# USB.net
KiCad netlist of a schematic drawn in Altium Designer
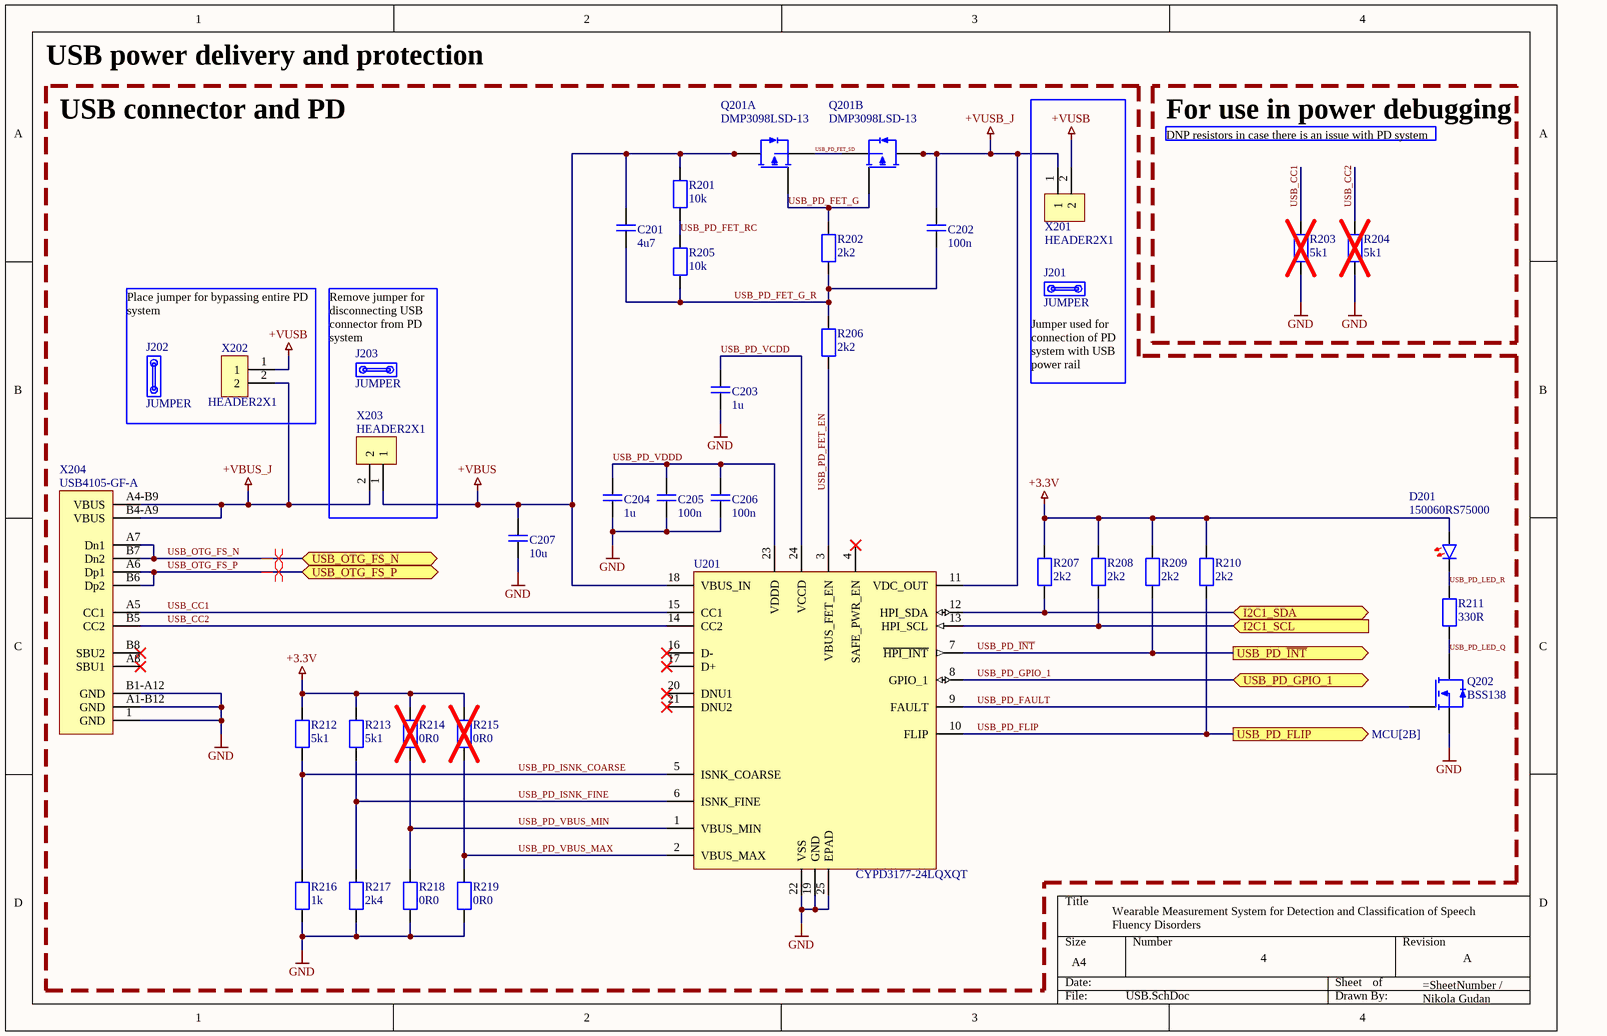
[diagram p0: USB.SchDoc]

(export (version "E")
  (design (tool "Eeschema 10.0.6"))
  (components
    (comp (ref "C201")
      (value "4u7")
      (footprint "CAPC0603")
      (description "Ceramic capacitor, VAL?,  VOL?, DIEL?")
      (fields (field (name "MFR") "?") (field (name "CHECKED") "Yes"))
      (libsource (lib "NG_Passive") (part "CAPC0603"))
    )
    (comp (ref "C202")
      (value "100n")
      (footprint "CAPC0603")
      (description "Ceramic capacitor, VAL?,  VOL?, DIEL?")
      (fields (field (name "MFR") "?") (field (name "CHECKED") "Yes"))
      (libsource (lib "NG_Passive") (part "CAPC0603"))
    )
    (comp (ref "C203")
      (value "1u")
      (footprint "CAPC0603")
      (description "Ceramic capacitor, VAL?,  VOL?, DIEL?")
      (fields (field (name "MFR") "?") (field (name "CHECKED") "Yes"))
      (libsource (lib "NG_Passive") (part "CAPC0603"))
    )
    (comp (ref "C204")
      (value "1u")
      (footprint "CAPC0603")
      (description "Ceramic capacitor, VAL?,  VOL?, DIEL?")
      (fields (field (name "MFR") "?") (field (name "CHECKED") "Yes"))
      (libsource (lib "NG_Passive") (part "CAPC0603"))
    )
    (comp (ref "C205")
      (value "100n")
      (footprint "CAPC0603")
      (description "Ceramic capacitor, VAL?,  VOL?, DIEL?")
      (fields (field (name "MFR") "?") (field (name "CHECKED") "Yes"))
      (libsource (lib "NG_Passive") (part "CAPC0603"))
    )
    (comp (ref "C206")
      (value "100n")
      (footprint "CAPC0603")
      (description "Ceramic capacitor, VAL?,  VOL?, DIEL?")
      (fields (field (name "MFR") "?") (field (name "CHECKED") "Yes"))
      (libsource (lib "NG_Passive") (part "CAPC0603"))
    )
    (comp (ref "C207")
      (value "10u")
      (footprint "CAPC0603")
      (description "Ceramic capacitor, VAL?,  VOL?, DIEL?")
      (fields (field (name "MFR") "?") (field (name "CHECKED") "Yes"))
      (libsource (lib "NG_Passive") (part "CAPC0603"))
    )
    (comp (ref "D201")
      (value "150060RS75000")
      (footprint "LED0603")
      (description "LED Red, 2.3V, 20mA")
      (fields
        (field (name "MFR") "Würth Elektronik")
        (field (name "LCSC PART NUMBER") "C497931")
        (field (name "CHECKED") "Yes")
      )
      (libsource (lib "NG_Active") (part "HL-PST-1608S9AC-04"))
    )
    (comp (ref "J201")
      (value "JUMPER")
      (description "Open Top 3A 2.54mm P=2.54mm Shunts & Jumpers ROHS")
      (fields
        (field (name "MFR") "Kycon, Inc.")
        (field (name "LCSC PART NUMBER") "C5305")
        (field (name "CHECKED") "Yes")
      )
      (libsource (lib "NG_Mechanical") (part "JUMPER"))
    )
    (comp (ref "J202")
      (value "JUMPER")
      (description "Open Top 3A 2.54mm P=2.54mm Shunts & Jumpers ROHS")
      (fields
        (field (name "MFR") "Kycon, Inc.")
        (field (name "LCSC PART NUMBER") "C5305")
        (field (name "CHECKED") "Yes")
      )
      (libsource (lib "NG_Mechanical") (part "JUMPER"))
    )
    (comp (ref "J203")
      (value "JUMPER")
      (description "Open Top 3A 2.54mm P=2.54mm Shunts & Jumpers ROHS")
      (fields
        (field (name "MFR") "Kycon, Inc.")
        (field (name "LCSC PART NUMBER") "C5305")
        (field (name "CHECKED") "Yes")
      )
      (libsource (lib "NG_Mechanical") (part "JUMPER"))
    )
    (comp (ref "Q201")
      (value "DMP3098LSD-13")
      (footprint "SOIC127P620X175-8")
      (description "MOSFET 2P-CH 30V 4.4A 8-SOIC")
      (fields
        (field (name "MFR") "Diodes Incorporated")
        (field (name "LCSC PART NUMBER") "C531177")
        (field (name "CHECKED") "Yes")
      )
      (libsource (lib "NG_Active") (part "DMP3098LSD-13"))
    )
    (comp (ref "Q202")
      (value "BSS138")
      (footprint "SOT190P240X290-3")
      (description "MOSFET N-CH 50V 220MA SOT23-3")
      (fields
        (field (name "MFR") "onsemi")
        (field (name "LCSC PART NUMBER") "C52895")
        (field (name "CHECKED") "Yes")
      )
      (libsource (lib "NG_Active") (part "BSS138"))
    )
    (comp (ref "R201")
      (value "10k")
      (footprint "RESC0603")
      (description "Thick film resistor, VAL?, POW?")
      (fields (field (name "MFR") "?") (field (name "CHECKED") "Yes"))
      (libsource (lib "NG_Passive") (part "RES0603"))
    )
    (comp (ref "R202")
      (value "2k2")
      (footprint "RESC0603")
      (description "Thick film resistor, VAL?, POW?")
      (fields (field (name "MFR") "?") (field (name "CHECKED") "Yes"))
      (libsource (lib "NG_Passive") (part "RES0603"))
    )
    (comp (ref "R203")
      (value "5k1")
      (footprint "RESC0603")
      (description "Thick film resistor, VAL?, POW?")
      (fields (field (name "MFR") "?") (field (name "CHECKED") "Yes"))
      (libsource (lib "NG_Passive") (part "RES0603"))
    )
    (comp (ref "R204")
      (value "5k1")
      (footprint "RESC0603")
      (description "Thick film resistor, VAL?, POW?")
      (fields (field (name "MFR") "?") (field (name "CHECKED") "Yes"))
      (libsource (lib "NG_Passive") (part "RES0603"))
    )
    (comp (ref "R205")
      (value "10k")
      (footprint "RESC0603")
      (description "Thick film resistor, VAL?, POW?")
      (fields (field (name "MFR") "?") (field (name "CHECKED") "Yes"))
      (libsource (lib "NG_Passive") (part "RES0603"))
    )
    (comp (ref "R206")
      (value "2k2")
      (footprint "RESC0603")
      (description "Thick film resistor, VAL?, POW?")
      (fields (field (name "MFR") "?") (field (name "CHECKED") "Yes"))
      (libsource (lib "NG_Passive") (part "RES0603"))
    )
    (comp (ref "R207")
      (value "2k2")
      (footprint "RESC0603")
      (description "Thick film resistor, VAL?, POW?")
      (fields (field (name "MFR") "?") (field (name "CHECKED") "Yes"))
      (libsource (lib "NG_Passive") (part "RES0603"))
    )
    (comp (ref "R208")
      (value "2k2")
      (footprint "RESC0603")
      (description "Thick film resistor, VAL?, POW?")
      (fields (field (name "MFR") "?") (field (name "CHECKED") "Yes"))
      (libsource (lib "NG_Passive") (part "RES0603"))
    )
    (comp (ref "R209")
      (value "2k2")
      (footprint "RESC0603")
      (description "Thick film resistor, VAL?, POW?")
      (fields (field (name "MFR") "?") (field (name "CHECKED") "Yes"))
      (libsource (lib "NG_Passive") (part "RES0603"))
    )
    (comp (ref "R210")
      (value "2k2")
      (footprint "RESC0603")
      (description "Thick film resistor, VAL?, POW?")
      (fields (field (name "MFR") "?") (field (name "CHECKED") "Yes"))
      (libsource (lib "NG_Passive") (part "RES0603"))
    )
    (comp (ref "R211")
      (value "330R")
      (footprint "RESC0603")
      (description "Thick film resistor, VAL?, POW?")
      (fields (field (name "MFR") "?") (field (name "CHECKED") "Yes"))
      (libsource (lib "NG_Passive") (part "RES0603"))
    )
    (comp (ref "R212")
      (value "5k1")
      (footprint "RESC0603")
      (description "Thick film resistor, VAL?, POW?")
      (fields (field (name "MFR") "?") (field (name "CHECKED") "Yes"))
      (libsource (lib "NG_Passive") (part "RES0603"))
    )
    (comp (ref "R213")
      (value "5k1")
      (footprint "RESC0603")
      (description "Thick film resistor, VAL?, POW?")
      (fields (field (name "MFR") "?") (field (name "CHECKED") "Yes"))
      (libsource (lib "NG_Passive") (part "RES0603"))
    )
    (comp (ref "R214")
      (value "0R0")
      (footprint "RESC0603")
      (description "Thick film resistor, VAL?, POW?")
      (fields (field (name "MFR") "?") (field (name "CHECKED") "Yes"))
      (libsource (lib "NG_Passive") (part "RES0603"))
    )
    (comp (ref "R215")
      (value "0R0")
      (footprint "RESC0603")
      (description "Thick film resistor, VAL?, POW?")
      (fields (field (name "MFR") "?") (field (name "CHECKED") "Yes"))
      (libsource (lib "NG_Passive") (part "RES0603"))
    )
    (comp (ref "R216")
      (value "1k")
      (footprint "RESC0603")
      (description "Thick film resistor, VAL?, POW?")
      (fields (field (name "MFR") "?") (field (name "CHECKED") "Yes"))
      (libsource (lib "NG_Passive") (part "RES0603"))
    )
    (comp (ref "R217")
      (value "2k4")
      (footprint "RESC0603")
      (description "Thick film resistor, VAL?, POW?")
      (fields (field (name "MFR") "?") (field (name "CHECKED") "Yes"))
      (libsource (lib "NG_Passive") (part "RES0603"))
    )
    (comp (ref "R218")
      (value "0R0")
      (footprint "RESC0603")
      (description "Thick film resistor, VAL?, POW?")
      (fields (field (name "MFR") "?") (field (name "CHECKED") "Yes"))
      (libsource (lib "NG_Passive") (part "RES0603"))
    )
    (comp (ref "R219")
      (value "0R0")
      (footprint "RESC0603")
      (description "Thick film resistor, VAL?, POW?")
      (fields (field (name "MFR") "?") (field (name "CHECKED") "Yes"))
      (libsource (lib "NG_Passive") (part "RES0603"))
    )
    (comp (ref "U201")
      (value "CYPD3177-24LQXQT")
      (footprint "QFN50P410X410X100-24EP")
      (description "Generic Description")
      (fields
        (field (name "MFR") "Infineon Technologies")
        (field (name "LCSC PART NUMBER") "C5904158")
        (field (name "CHECKED") "Yes")
      )
      (libsource (lib "NG_Analog") (part "CYPD3177-24LQXQT"))
    )
    (comp (ref "X201")
      (value "HEADER2X1")
      (footprint "HDRV2W64P254_2X1_508X254X1150")
      (description "Pin Header 2x1, P2.54")
      (fields
        (field (name "MFR") "Adam Tech")
        (field (name "LCSC PART NUMBER") "C2883961")
        (field (name "CHECKED") "Yes")
      )
      (libsource (lib "NG_Mechanical") (part "HEADER2X1"))
    )
    (comp (ref "X202")
      (value "HEADER2X1")
      (footprint "HDRV2W64P254_2X1_508X254X1150")
      (description "Pin Header 2x1, P2.54")
      (fields
        (field (name "MFR") "Adam Tech")
        (field (name "LCSC PART NUMBER") "C2883961")
        (field (name "CHECKED") "Yes")
      )
      (libsource (lib "") (part "HEADER2X1_1"))
    )
    (comp (ref "X203")
      (value "HEADER2X1")
      (footprint "HDRV2W64P254_2X1_508X254X1150")
      (description "Pin Header 2x1, P2.54")
      (fields
        (field (name "MFR") "Adam Tech")
        (field (name "LCSC PART NUMBER") "C2883961")
        (field (name "CHECKED") "Yes")
      )
      (libsource (lib "") (part "HEADER2X1_2"))
    )
    (comp (ref "X204")
      (value "USB4105-GF-A")
      (footprint "GCT_USB4105-GF-A")
      (description "USB TYPE-C 3.1, 3A")
      (fields
        (field (name "MFR") "GCT")
        (field (name "LCSC PART NUMBER") "C2997433")
        (field (name "CHECKED") "Yes")
      )
      (libsource (lib "NG_Mechanical") (part "CONN USB 2.0 TYPE C"))
    )
  )
  (nets
    (net (code "1") (name "+3.3V") (class "Default")
      (node (ref "D201") (pin "2") (pinfunction "2_2") (pintype "passive"))
      (node (ref "R207") (pin "2") (pinfunction "2_2") (pintype "passive"))
      (node (ref "R208") (pin "2") (pinfunction "2_2") (pintype "passive"))
      (node (ref "R209") (pin "2") (pinfunction "2_2") (pintype "passive"))
      (node (ref "R210") (pin "2") (pinfunction "2_2") (pintype "passive"))
      (node (ref "R212") (pin "2") (pinfunction "2_2") (pintype "passive"))
      (node (ref "R213") (pin "2") (pinfunction "2_2") (pintype "passive"))
      (node (ref "R214") (pin "2") (pinfunction "2_2") (pintype "passive"))
      (node (ref "R215") (pin "2") (pinfunction "2_2") (pintype "passive"))
    )
    (net (code "2") (name "+VBUS") (class "Default")
      (node (ref "C201") (pin "2") (pinfunction "2_2") (pintype "passive"))
      (node (ref "C207") (pin "2") (pinfunction "2_2") (pintype "passive"))
      (node (ref "Q201") (pin "7") (pinfunction "D1_7") (pintype "power_in"))
      (node (ref "Q201") (pin "8") (pinfunction "D1_8") (pintype "power_in"))
      (node (ref "R201") (pin "2") (pinfunction "2_2") (pintype "passive"))
      (node (ref "U201") (pin "18") (pinfunction "VBUS_IN_18") (pintype "power_in"))
      (node (ref "X203") (pin "1") (pinfunction "1_1") (pintype "passive"))
    )
    (net (code "3") (name "+VBUS_J") (class "Default")
      (node (ref "X202") (pin "2") (pinfunction "2_2") (pintype "passive"))
      (node (ref "X203") (pin "2") (pinfunction "2_2") (pintype "passive"))
      (node (ref "X204") (pin "A4-B9") (pinfunction "VBUS_A4-B9") (pintype "power_in"))
      (node (ref "X204") (pin "B4-A9") (pinfunction "VBUS_B4-A9") (pintype "power_in"))
    )
    (net (code "4") (name "+VUSB") (class "Default")
      (node (ref "X201") (pin "2") (pinfunction "2_2") (pintype "passive"))
      (node (ref "X202") (pin "1") (pinfunction "1_1") (pintype "passive"))
    )
    (net (code "5") (name "+VUSB_J") (class "Default")
      (node (ref "C202") (pin "2") (pinfunction "2_2") (pintype "passive"))
      (node (ref "Q201") (pin "5") (pinfunction "D2_5") (pintype "power_in"))
      (node (ref "Q201") (pin "6") (pinfunction "D2_6") (pintype "power_in"))
      (node (ref "U201") (pin "11") (pinfunction "VDC_OUT_11") (pintype "passive"))
      (node (ref "X201") (pin "1") (pinfunction "1_1") (pintype "passive"))
    )
    (net (code "6") (name "/I2C1_SCL") (class "Default")
      (node (ref "R208") (pin "1") (pinfunction "1_1") (pintype "passive"))
      (node (ref "U201") (pin "13") (pinfunction "HPI_SCL_13") (pintype "input"))
    )
    (net (code "7") (name "/I2C1_SDA") (class "Default")
      (node (ref "R207") (pin "1") (pinfunction "1_1") (pintype "passive"))
      (node (ref "U201") (pin "12") (pinfunction "HPI_SDA_12") (pintype "bidirectional"))
    )
    (net (code "8") (name "/USB_CC1") (class "Default")
      (node (ref "R203") (pin "2") (pinfunction "2_2") (pintype "passive"))
      (node (ref "U201") (pin "15") (pinfunction "CC1_15") (pintype "passive"))
      (node (ref "X204") (pin "A5") (pinfunction "CC1_A5") (pintype "passive"))
    )
    (net (code "9") (name "/USB_CC2") (class "Default")
      (node (ref "R204") (pin "2") (pinfunction "2_2") (pintype "passive"))
      (node (ref "U201") (pin "14") (pinfunction "CC2_14") (pintype "passive"))
      (node (ref "X204") (pin "B5") (pinfunction "CC2_B5") (pintype "passive"))
    )
    (net (code "10") (name "/USB_OTG_FS_N") (class "Default")
      (node (ref "X204") (pin "A7") (pinfunction "Dn1_A7") (pintype "passive"))
      (node (ref "X204") (pin "B7") (pinfunction "Dn2_B7") (pintype "passive"))
    )
    (net (code "11") (name "/USB_OTG_FS_P") (class "Default")
      (node (ref "X204") (pin "A6") (pinfunction "Dp1_A6") (pintype "passive"))
      (node (ref "X204") (pin "B6") (pinfunction "Dp2_B6") (pintype "passive"))
    )
    (net (code "12") (name "/USB_PD_FAULT") (class "Default")
      (node (ref "Q202") (pin "1") (pinfunction "G_1") (pintype "passive"))
      (node (ref "U201") (pin "9") (pinfunction "FAULT_9") (pintype "passive"))
    )
    (net (code "13") (name "/USB_PD_FET_EN") (class "Default")
      (node (ref "R206") (pin "1") (pinfunction "1_1") (pintype "passive"))
      (node (ref "U201") (pin "3") (pinfunction "VBUS_FET_EN_3") (pintype "passive"))
    )
    (net (code "14") (name "/USB_PD_FET_G") (class "Default")
      (node (ref "Q201") (pin "2") (pinfunction "G1_2") (pintype "power_in"))
      (node (ref "Q201") (pin "4") (pinfunction "G2_4") (pintype "power_in"))
      (node (ref "R202") (pin "2") (pinfunction "2_2") (pintype "passive"))
    )
    (net (code "15") (name "/USB_PD_FET_G_R") (class "Default")
      (node (ref "C201") (pin "1") (pinfunction "1_1") (pintype "passive"))
      (node (ref "C202") (pin "1") (pinfunction "1_1") (pintype "passive"))
      (node (ref "R202") (pin "1") (pinfunction "1_1") (pintype "passive"))
      (node (ref "R205") (pin "1") (pinfunction "1_1") (pintype "passive"))
      (node (ref "R206") (pin "2") (pinfunction "2_2") (pintype "passive"))
    )
    (net (code "16") (name "/USB_PD_FET_RC") (class "Default")
      (node (ref "R201") (pin "1") (pinfunction "1_1") (pintype "passive"))
      (node (ref "R205") (pin "2") (pinfunction "2_2") (pintype "passive"))
    )
    (net (code "17") (name "/USB_PD_FET_SD") (class "Default")
      (node (ref "Q201") (pin "1") (pinfunction "S1_1") (pintype "power_in"))
      (node (ref "Q201") (pin "3") (pinfunction "S2_3") (pintype "power_in"))
    )
    (net (code "18") (name "/USB_PD_FLIP") (class "Default")
      (node (ref "R210") (pin "1") (pinfunction "1_1") (pintype "passive"))
      (node (ref "U201") (pin "10") (pinfunction "FLIP_10") (pintype "passive"))
    )
    (net (code "19") (name "/USB_PD_GPIO_1") (class "Default")
      (node (ref "U201") (pin "8") (pinfunction "GPIO_1_8") (pintype "bidirectional"))
    )
    (net (code "20") (name "/USB_PD_ISNK_COARSE") (class "Default")
      (node (ref "R212") (pin "1") (pinfunction "1_1") (pintype "passive"))
      (node (ref "R216") (pin "2") (pinfunction "2_2") (pintype "passive"))
      (node (ref "U201") (pin "5") (pinfunction "ISNK_COARSE_5") (pintype "passive"))
    )
    (net (code "21") (name "/USB_PD_ISNK_FINE") (class "Default")
      (node (ref "R213") (pin "1") (pinfunction "1_1") (pintype "passive"))
      (node (ref "R217") (pin "2") (pinfunction "2_2") (pintype "passive"))
      (node (ref "U201") (pin "6") (pinfunction "ISNK_FINE_6") (pintype "passive"))
    )
    (net (code "22") (name "/USB_PD_LED_Q") (class "Default")
      (node (ref "Q202") (pin "3") (pinfunction "D_3") (pintype "passive"))
      (node (ref "R211") (pin "1") (pinfunction "1_1") (pintype "passive"))
    )
    (net (code "23") (name "/USB_PD_LED_R") (class "Default")
      (node (ref "D201") (pin "1") (pinfunction "1_1") (pintype "passive"))
      (node (ref "R211") (pin "2") (pinfunction "2_2") (pintype "passive"))
    )
    (net (code "24") (name "/USB_PD_VBUS_MAX") (class "Default")
      (node (ref "R215") (pin "1") (pinfunction "1_1") (pintype "passive"))
      (node (ref "R219") (pin "2") (pinfunction "2_2") (pintype "passive"))
      (node (ref "U201") (pin "2") (pinfunction "VBUS_MAX_2") (pintype "passive"))
    )
    (net (code "25") (name "/USB_PD_VBUS_MIN") (class "Default")
      (node (ref "R214") (pin "1") (pinfunction "1_1") (pintype "passive"))
      (node (ref "R218") (pin "2") (pinfunction "2_2") (pintype "passive"))
      (node (ref "U201") (pin "1") (pinfunction "VBUS_MIN_1") (pintype "passive"))
    )
    (net (code "26") (name "/USB_PD_VCDD") (class "Default")
      (node (ref "C203") (pin "2") (pinfunction "2_2") (pintype "passive"))
      (node (ref "U201") (pin "24") (pinfunction "VCCD_24") (pintype "power_in"))
    )
    (net (code "27") (name "/USB_PD_VDDD") (class "Default")
      (node (ref "C204") (pin "2") (pinfunction "2_2") (pintype "passive"))
      (node (ref "C205") (pin "2") (pinfunction "2_2") (pintype "passive"))
      (node (ref "C206") (pin "2") (pinfunction "2_2") (pintype "passive"))
      (node (ref "U201") (pin "23") (pinfunction "VDDD_23") (pintype "power_in"))
    )
    (net (code "28") (name "/USB_PD_~{INT}") (class "Default")
      (node (ref "R209") (pin "1") (pinfunction "1_1") (pintype "passive"))
      (node (ref "U201") (pin "7") (pinfunction "~{HPI_INT}_7") (pintype "output"))
    )
    (net (code "29") (name "GND") (class "Default")
      (node (ref "C203") (pin "1") (pinfunction "1_1") (pintype "passive"))
      (node (ref "C204") (pin "1") (pinfunction "1_1") (pintype "passive"))
      (node (ref "C205") (pin "1") (pinfunction "1_1") (pintype "passive"))
      (node (ref "C206") (pin "1") (pinfunction "1_1") (pintype "passive"))
      (node (ref "C207") (pin "1") (pinfunction "1_1") (pintype "passive"))
      (node (ref "Q202") (pin "2") (pinfunction "S_2") (pintype "passive"))
      (node (ref "R203") (pin "1") (pinfunction "1_1") (pintype "passive"))
      (node (ref "R204") (pin "1") (pinfunction "1_1") (pintype "passive"))
      (node (ref "R216") (pin "1") (pinfunction "1_1") (pintype "passive"))
      (node (ref "R217") (pin "1") (pinfunction "1_1") (pintype "passive"))
      (node (ref "R218") (pin "1") (pinfunction "1_1") (pintype "passive"))
      (node (ref "R219") (pin "1") (pinfunction "1_1") (pintype "passive"))
      (node (ref "U201") (pin "19") (pinfunction "GND_19") (pintype "power_in"))
      (node (ref "U201") (pin "22") (pinfunction "VSS_22") (pintype "power_in"))
      (node (ref "U201") (pin "25") (pinfunction "EPAD_25") (pintype "power_in"))
      (node (ref "X204") (pin "1") (pinfunction "GND_1") (pintype "power_in"))
      (node (ref "X204") (pin "A1-B12") (pinfunction "GND_A1-B12") (pintype "power_in"))
      (node (ref "X204") (pin "B1-A12") (pinfunction "GND_B1-A12") (pintype "power_in"))
    )
    (net (code "30") (name "unconnected-(U201-D+-Pad17)") (class "Default")
      (node (ref "U201") (pin "17") (pinfunction "D+_17") (pintype "passive+no_connect"))
    )
    (net (code "31") (name "unconnected-(U201-D--Pad16)") (class "Default")
      (node (ref "U201") (pin "16") (pinfunction "D-_16") (pintype "passive+no_connect"))
    )
    (net (code "32") (name "unconnected-(U201-DNU1-Pad20)") (class "Default")
      (node (ref "U201") (pin "20") (pinfunction "DNU1_20") (pintype "passive+no_connect"))
    )
    (net (code "33") (name "unconnected-(U201-DNU2-Pad21)") (class "Default")
      (node (ref "U201") (pin "21") (pinfunction "DNU2_21") (pintype "passive+no_connect"))
    )
    (net (code "34") (name "unconnected-(U201-SAFE_PWR_EN-Pad4)") (class "Default")
      (node (ref "U201") (pin "4") (pinfunction "SAFE_PWR_EN_4") (pintype "passive+no_connect"))
    )
    (net (code "35") (name "unconnected-(X204-SBU1-PadA8)") (class "Default")
      (node (ref "X204") (pin "A8") (pinfunction "SBU1_A8") (pintype "passive+no_connect"))
    )
    (net (code "36") (name "unconnected-(X204-SBU2-PadB8)") (class "Default")
      (node (ref "X204") (pin "B8") (pinfunction "SBU2_B8") (pintype "passive+no_connect"))
    )
  )
)
